# -LTC3417.net
KiCad netlist of a schematic drawn in Altium Designer
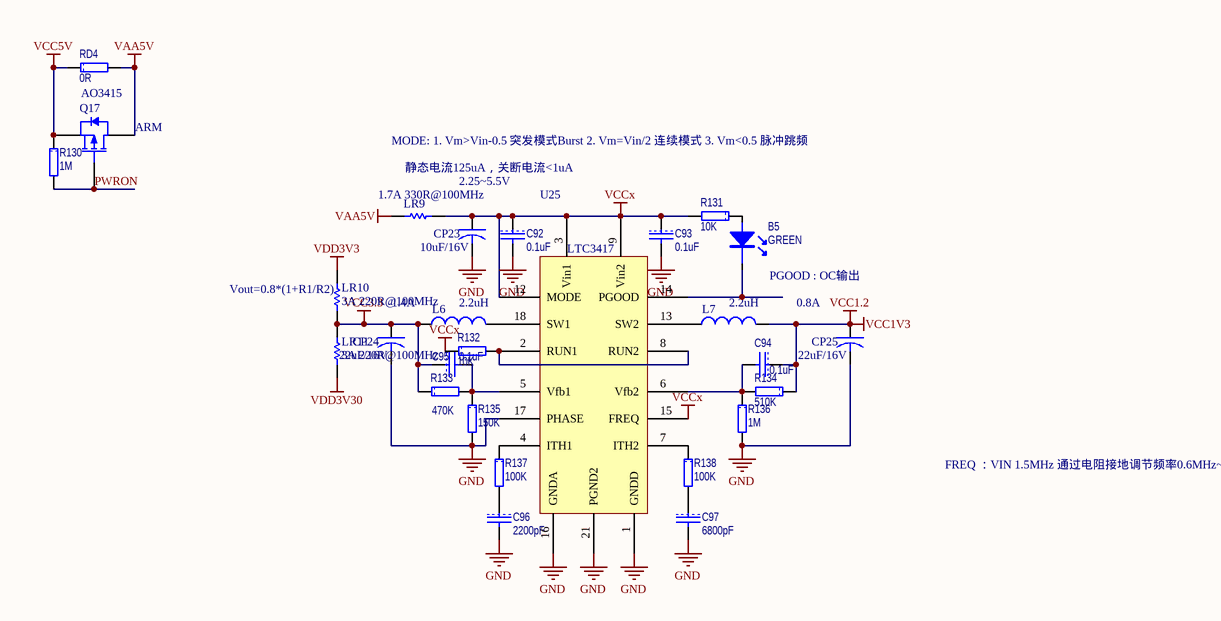
[diagram p0: -LTC3417.SchDoc]

(export (version "E")
  (design (tool "Eeschema 10.0.6"))
  (components
    (comp (ref "B5")
      (value "GREEN")
      (footprint "LED0805")
      (description "发光管")
      (libsource (lib "*") (part "LED"))
    )
    (comp (ref "C92")
      (value "0.1uF")
      (footprint "1608[0603]")
      (description "Capacitor")
      (fields (field (name "MANUFACTURER") "TDK"))
      (libsource (lib "*") (part "CAP"))
    )
    (comp (ref "C93")
      (value "0.1uF")
      (footprint "1608[0603]")
      (description "Capacitor")
      (fields (field (name "MANUFACTURER") "TDK"))
      (libsource (lib "*") (part "CAP"))
    )
    (comp (ref "C94")
      (value "0.1uF")
      (footprint "1608[0603]")
      (description "Capacitor")
      (fields (field (name "MANUFACTURER") "TDK"))
      (libsource (lib "*") (part "CAP"))
    )
    (comp (ref "C95")
      (value "0.1uF")
      (footprint "1608[0603]")
      (description "Capacitor")
      (fields (field (name "MANUFACTURER") "TDK"))
      (libsource (lib "*") (part "CAP"))
    )
    (comp (ref "C96")
      (value "2200pF")
      (footprint "1608[0603]")
      (description "Capacitor")
      (fields (field (name "MANUFACTURER") "TDK"))
      (libsource (lib "*") (part "CAP"))
    )
    (comp (ref "C97")
      (value "6800pF")
      (footprint "1608[0603]")
      (description "Capacitor")
      (fields (field (name "MANUFACTURER") "TDK"))
      (libsource (lib "*") (part "CAP"))
    )
    (comp (ref "CP23")
      (value "10uF/16V")
      (footprint "3216[1206]")
      (description "Tantalum Capacitor")
      (libsource (lib "*") (part "CAPACITOR"))
    )
    (comp (ref "CP24")
      (value "22uF/16V")
      (footprint "3216[1206]")
      (description "Tantalum Capacitor")
      (libsource (lib "*") (part "CAPACITOR"))
    )
    (comp (ref "CP25")
      (value "22uF/16V")
      (footprint "3216[1206]")
      (description "Tantalum Capacitor")
      (libsource (lib "*") (part "CAPACITOR"))
    )
    (comp (ref "L6")
      (value "2.2uH")
      (footprint "INDP5050X28N - duplicate")
      (description "Inductor")
      (fields (field (name "Comment") "CDRH4D22/HP 1R5") (field (name "PUBLISHER") "Altium Limited"))
      (libsource (lib "Miscellaneous Devices") (part "Inductor"))
    )
    (comp (ref "L7")
      (value "2.2uH")
      (footprint "INDP3232")
      (description "Inductor")
      (fields (field (name "Comment") "CDRH2D18/HP 2R2") (field (name "PUBLISHER") "Altium Limited"))
      (libsource (lib "Miscellaneous Devices") (part "Inductor"))
    )
    (comp (ref "LR9")
      (value "1.7A 330R@100MHz")
      (footprint "0603RV")
      (description "Semiconductor Resistor")
      (fields (field (name "Comment") "MPZ1608S331A") (field (name "PUBLISHER") "Altium Limited"))
      (libsource (lib "Miscellaneous Devices") (part "Res Semi"))
    )
    (comp (ref "LR10")
      (value "3A 220R@100MHz")
      (footprint "2012[0805]")
      (description "Semiconductor Resistor")
      (fields (field (name "Comment") "MPZ2012S221A") (field (name "PUBLISHER") "Altium Limited"))
      (libsource (lib "Miscellaneous Devices") (part "Res Semi"))
    )
    (comp (ref "LR11")
      (value "3A 220R@100MHz")
      (footprint "2012[0805]")
      (description "Semiconductor Resistor")
      (fields (field (name "Comment") "MPZ2012S221A") (field (name "PUBLISHER") "Altium Limited"))
      (libsource (lib "Miscellaneous Devices") (part "Res Semi"))
    )
    (comp (ref "Q17")
      (value "AO3415")
      (footprint "SOT23_N")
      (description "P-channel Enhancement Mode MOSFET")
      (fields (field (name "PUBLISHER") "Altium Limited"))
      (libsource (lib "Philips Discrete MOSFET - Low Power") (part "BSH205"))
    )
    (comp (ref "R130")
      (value "1M")
      (footprint "0603R")
      (description "RES")
      (fields (field (name "MANUFACTURER") "vishay"))
      (libsource (lib "*") (part "RES"))
    )
    (comp (ref "R131")
      (value "10K")
      (footprint "0603R")
      (description "RES")
      (fields (field (name "MANUFACTURER") "vishay"))
      (libsource (lib "*") (part "RES"))
    )
    (comp (ref "R132")
      (value "10K")
      (footprint "0603R")
      (description "RES")
      (libsource (lib "*") (part "RES"))
    )
    (comp (ref "R133")
      (value "470K")
      (footprint "0603R")
      (description "RES")
      (libsource (lib "*") (part "RES"))
    )
    (comp (ref "R134")
      (value "510K")
      (footprint "0603R")
      (description "RES")
      (libsource (lib "*") (part "RES"))
    )
    (comp (ref "R135")
      (value "150K")
      (footprint "0603R")
      (description "RES")
      (libsource (lib "*") (part "RES"))
    )
    (comp (ref "R136")
      (value "1M")
      (footprint "0603R")
      (description "RES")
      (libsource (lib "*") (part "RES"))
    )
    (comp (ref "R137")
      (value "100K")
      (footprint "0603R")
      (description "RES")
      (libsource (lib "*") (part "RES"))
    )
    (comp (ref "R138")
      (value "100K")
      (footprint "0603R")
      (description "RES")
      (libsource (lib "*") (part "RES"))
    )
    (comp (ref "RD4")
      (value "0R")
      (footprint "0603RN")
      (description "RES")
      (fields (field (name "MANUFACTURER") "vishay"))
      (libsource (lib "*") (part "RES"))
    )
    (comp (ref "U25")
      (value "LTC3417")
      (footprint "TSSOP20-FE/CA")
      (description "电源管理")
      (libsource (lib "S3C2440V9") (part "LTC3417"))
    )
  )
  (nets
    (net (code "1") (name "/PWRON") (class "Default")
      (node (ref "Q17") (pin "1") (pinfunction "G_1") (pintype "passive"))
      (node (ref "R130") (pin "2") (pinfunction "2_2") (pintype "passive"))
    )
    (net (code "2") (name "GND") (class "Default")
      (node (ref "C92") (pin "2") (pinfunction "2_2") (pintype "passive"))
      (node (ref "C93") (pin "2") (pinfunction "2_2") (pintype "passive"))
      (node (ref "C96") (pin "2") (pinfunction "2_2") (pintype "passive"))
      (node (ref "C97") (pin "2") (pinfunction "2_2") (pintype "passive"))
      (node (ref "CP23") (pin "2") (pinfunction "2_2") (pintype "passive"))
      (node (ref "CP24") (pin "2") (pinfunction "2_2") (pintype "passive"))
      (node (ref "CP25") (pin "2") (pinfunction "2_2") (pintype "passive"))
      (node (ref "R135") (pin "2") (pinfunction "2_2") (pintype "passive"))
      (node (ref "R136") (pin "2") (pinfunction "2_2") (pintype "passive"))
      (node (ref "U25") (pin "1") (pinfunction "GNDD_1") (pintype "passive"))
      (node (ref "U25") (pin "16") (pinfunction "GNDA_16") (pintype "passive"))
      (node (ref "U25") (pin "17") (pinfunction "PHASE_17") (pintype "passive"))
      (node (ref "U25") (pin "21") (pinfunction "PGND2_21") (pintype "passive"))
    )
    (net (code "3") (name "Net-(B5-Pad1)") (class "Default")
      (node (ref "B5") (pin "1") (pinfunction "1_1") (pintype "passive"))
      (node (ref "R131") (pin "1") (pinfunction "1_1") (pintype "passive"))
    )
    (net (code "4") (name "Net-(C96-Pad1)") (class "Default")
      (node (ref "C96") (pin "1") (pinfunction "1_1") (pintype "passive"))
      (node (ref "R137") (pin "2") (pinfunction "2_2") (pintype "passive"))
    )
    (net (code "5") (name "Net-(C97-Pad1)") (class "Default")
      (node (ref "C97") (pin "1") (pinfunction "1_1") (pintype "passive"))
      (node (ref "R138") (pin "2") (pinfunction "2_2") (pintype "passive"))
    )
    (net (code "6") (name "Net-(U25-ITH1)") (class "Default")
      (node (ref "R137") (pin "1") (pinfunction "1_1") (pintype "passive"))
      (node (ref "U25") (pin "4") (pinfunction "ITH1_4") (pintype "passive"))
    )
    (net (code "7") (name "Net-(U25-ITH2)") (class "Default")
      (node (ref "R138") (pin "1") (pinfunction "1_1") (pintype "passive"))
      (node (ref "U25") (pin "7") (pinfunction "ITH2_7") (pintype "passive"))
    )
    (net (code "8") (name "Net-(U25-PGOOD)") (class "Default")
      (node (ref "B5") (pin "2") (pinfunction "2_2") (pintype "passive"))
      (node (ref "U25") (pin "14") (pinfunction "PGOOD_14") (pintype "passive"))
    )
    (net (code "9") (name "Net-(U25-RUN1)") (class "Default")
      (node (ref "R132") (pin "2") (pinfunction "2_2") (pintype "passive"))
      (node (ref "U25") (pin "2") (pinfunction "RUN1_2") (pintype "passive"))
      (node (ref "U25") (pin "8") (pinfunction "RUN2_8") (pintype "passive"))
    )
    (net (code "10") (name "Net-(U25-SW1)") (class "Default")
      (node (ref "L6") (pin "2") (pinfunction "2_2") (pintype "passive"))
      (node (ref "U25") (pin "18") (pinfunction "SW1_18") (pintype "passive"))
    )
    (net (code "11") (name "Net-(U25-SW2)") (class "Default")
      (node (ref "L7") (pin "1") (pinfunction "1_1") (pintype "passive"))
      (node (ref "U25") (pin "13") (pinfunction "SW2_13") (pintype "passive"))
    )
    (net (code "12") (name "Net-(U25-Vfb1)") (class "Default")
      (node (ref "C95") (pin "2") (pinfunction "2_2") (pintype "passive"))
      (node (ref "R133") (pin "2") (pinfunction "2_2") (pintype "passive"))
      (node (ref "R135") (pin "1") (pinfunction "1_1") (pintype "passive"))
      (node (ref "U25") (pin "5") (pinfunction "Vfb1_5") (pintype "passive"))
    )
    (net (code "13") (name "Net-(U25-Vfb2)") (class "Default")
      (node (ref "C94") (pin "2") (pinfunction "2_2") (pintype "passive"))
      (node (ref "R134") (pin "2") (pinfunction "2_2") (pintype "passive"))
      (node (ref "R136") (pin "1") (pinfunction "1_1") (pintype "passive"))
      (node (ref "U25") (pin "6") (pinfunction "Vfb2_6") (pintype "passive"))
    )
    (net (code "14") (name "VAA5V") (class "Default")
      (node (ref "LR9") (pin "1") (pinfunction "1_1") (pintype "passive"))
      (node (ref "Q17") (pin "3") (pinfunction "D_3") (pintype "passive"))
      (node (ref "RD4") (pin "2") (pinfunction "2_2") (pintype "passive"))
    )
    (net (code "15") (name "VCC1.2") (class "Default")
      (node (ref "C94") (pin "1") (pinfunction "1_1") (pintype "passive"))
      (node (ref "CP25") (pin "1") (pinfunction "1_1") (pintype "passive"))
      (node (ref "L7") (pin "2") (pinfunction "2_2") (pintype "passive"))
      (node (ref "R134") (pin "1") (pinfunction "1_1") (pintype "passive"))
    )
    (net (code "16") (name "VCC3.3") (class "Default")
      (node (ref "C95") (pin "1") (pinfunction "1_1") (pintype "passive"))
      (node (ref "CP24") (pin "1") (pinfunction "1_1") (pintype "passive"))
      (node (ref "L6") (pin "1") (pinfunction "1_1") (pintype "passive"))
      (node (ref "LR10") (pin "1") (pinfunction "1_1") (pintype "passive"))
      (node (ref "LR11") (pin "2") (pinfunction "2_2") (pintype "passive"))
      (node (ref "R133") (pin "1") (pinfunction "1_1") (pintype "passive"))
    )
    (net (code "17") (name "VCC5V") (class "Default")
      (node (ref "Q17") (pin "2") (pinfunction "S_2") (pintype "passive"))
      (node (ref "R130") (pin "1") (pinfunction "1_1") (pintype "passive"))
      (node (ref "RD4") (pin "1") (pinfunction "1_1") (pintype "passive"))
    )
    (net (code "18") (name "VCCx") (class "Default")
      (node (ref "C92") (pin "1") (pinfunction "1_1") (pintype "passive"))
      (node (ref "C93") (pin "1") (pinfunction "1_1") (pintype "passive"))
      (node (ref "CP23") (pin "1") (pinfunction "1_1") (pintype "passive"))
      (node (ref "LR9") (pin "2") (pinfunction "2_2") (pintype "passive"))
      (node (ref "R131") (pin "2") (pinfunction "2_2") (pintype "passive"))
      (node (ref "R132") (pin "1") (pinfunction "1_1") (pintype "passive"))
      (node (ref "U25") (pin "12") (pinfunction "MODE_12") (pintype "passive"))
      (node (ref "U25") (pin "15") (pinfunction "FREQ_15") (pintype "passive"))
      (node (ref "U25") (pin "3") (pinfunction "Vin1_3") (pintype "passive"))
      (node (ref "U25") (pin "9") (pinfunction "Vin2_9") (pintype "passive"))
    )
    (net (code "19") (name "VDD3V3") (class "Default")
      (node (ref "LR10") (pin "2") (pinfunction "2_2") (pintype "passive"))
    )
    (net (code "20") (name "VDD3V30") (class "Default")
      (node (ref "LR11") (pin "1") (pinfunction "1_1") (pintype "passive"))
    )
    (net (code "21") (name "unconnected-(U25-GNDD-Pad20)") (class "Default")
      (node (ref "U25") (pin "20") (pinfunction "GNDD_20") (pintype "passive"))
    )
    (net (code "22") (name "unconnected-(U25-PGND1-Pad19)") (class "Default")
      (node (ref "U25") (pin "19") (pinfunction "PGND1_19") (pintype "passive"))
    )
    (net (code "23") (name "unconnected-(U25-PGND2-Pad10)") (class "Default")
      (node (ref "U25") (pin "10") (pinfunction "PGND2_10") (pintype "passive"))
    )
    (net (code "24") (name "unconnected-(U25-PGND2-Pad11)") (class "Default")
      (node (ref "U25") (pin "11") (pinfunction "PGND2_11") (pintype "passive"))
    )
  )
)
